# dc_dc.net
KiCad netlist of a schematic drawn in Altium Designer
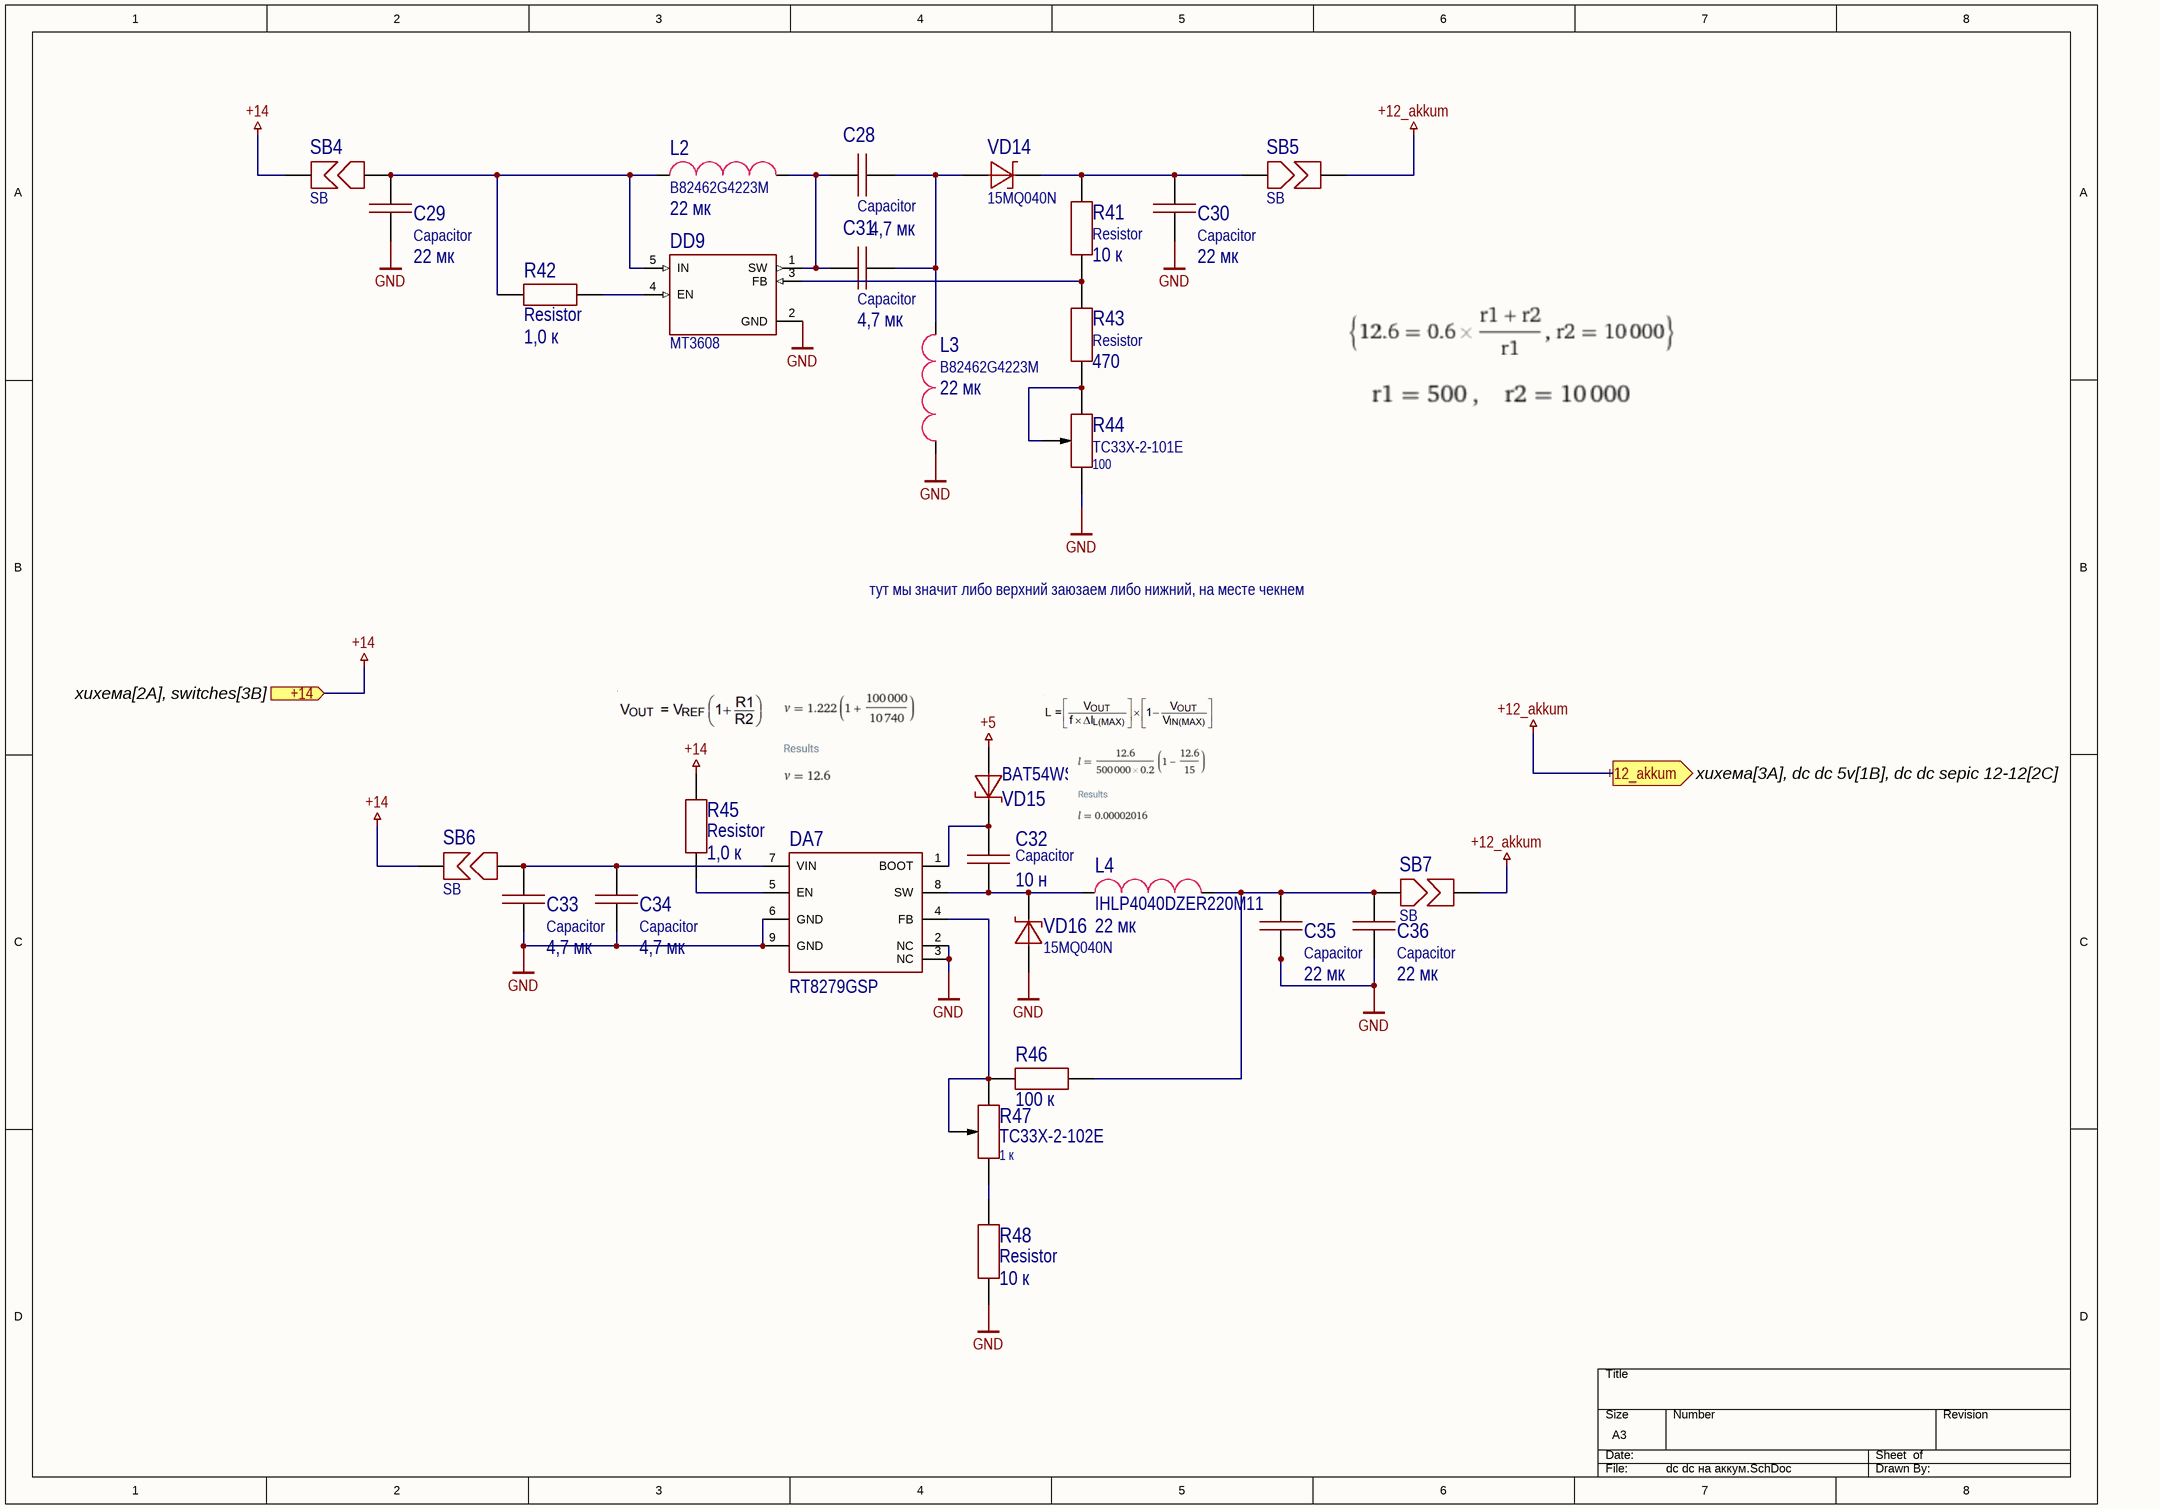
[diagram p0: dc dc на аккум.SchDoc]

(export (version "E")
  (design (tool "Eeschema 10.0.6"))
  (components
    (comp (ref "C28")
      (value "Capacitor")
      (footprint "1206C")
      (description "Конденсатор")
      (fields
        (field (name "ALTIUM_VALUE") "4,7 мк")
        (field (name "PART NUMBER") "Capacitor_4,7u_10_50V_X7R_1206C")
        (field (name "TOLERANCE") "0,1")
      )
      (libsource (lib "Hydrolib") (part "Capacitor"))
    )
    (comp (ref "C29")
      (value "Capacitor")
      (footprint "1210C")
      (description "Конденсатор")
      (fields
        (field (name "ALTIUM_VALUE") "22 мк")
        (field (name "PART NUMBER") "Capacitor_22u_10_25V_X7R_1210C")
        (field (name "TOLERANCE") "0,1")
      )
      (libsource (lib "Hydrolib") (part "Capacitor"))
    )
    (comp (ref "C30")
      (value "Capacitor")
      (footprint "1210C")
      (description "Конденсатор")
      (fields
        (field (name "ALTIUM_VALUE") "22 мк")
        (field (name "PART NUMBER") "Capacitor_22u_10_25V_X7R_1210C")
        (field (name "TOLERANCE") "0,1")
      )
      (libsource (lib "Hydrolib") (part "Capacitor"))
    )
    (comp (ref "C31")
      (value "Capacitor")
      (footprint "1206C")
      (description "Конденсатор")
      (fields
        (field (name "ALTIUM_VALUE") "4,7 мк")
        (field (name "PART NUMBER") "Capacitor_4,7u_10_50V_X7R_1206C")
        (field (name "TOLERANCE") "0,1")
      )
      (libsource (lib "Hydrolib") (part "Capacitor"))
    )
    (comp (ref "C32")
      (value "Capacitor")
      (footprint "0603C")
      (description "Конденсатор")
      (fields
        (field (name "ALTIUM_VALUE") "10 н")
        (field (name "PART NUMBER") "Capacitor_10n_10_50V_X7R_0603C")
        (field (name "TOLERANCE") "0,1")
      )
      (libsource (lib "Hydrolib") (part "Capacitor"))
    )
    (comp (ref "C33")
      (value "Capacitor")
      (footprint "1206C")
      (description "Конденсатор")
      (fields
        (field (name "ALTIUM_VALUE") "4,7 мк")
        (field (name "PART NUMBER") "Capacitor_4,7u_10_50V_X7R_1206C")
        (field (name "TOLERANCE") "0,1")
      )
      (libsource (lib "Hydrolib") (part "Capacitor"))
    )
    (comp (ref "C34")
      (value "Capacitor")
      (footprint "1206C")
      (description "Конденсатор")
      (fields
        (field (name "ALTIUM_VALUE") "4,7 мк")
        (field (name "PART NUMBER") "Capacitor_4,7u_10_50V_X7R_1206C")
        (field (name "TOLERANCE") "0,1")
      )
      (libsource (lib "Hydrolib") (part "Capacitor"))
    )
    (comp (ref "C35")
      (value "Capacitor")
      (footprint "1210C")
      (description "Конденсатор")
      (fields
        (field (name "ALTIUM_VALUE") "22 мк")
        (field (name "PART NUMBER") "Capacitor_22u_10_25V_X7R_1210C")
        (field (name "TOLERANCE") "0,1")
      )
      (libsource (lib "Hydrolib") (part "Capacitor"))
    )
    (comp (ref "C36")
      (value "Capacitor")
      (footprint "1210C")
      (description "Конденсатор")
      (fields
        (field (name "ALTIUM_VALUE") "22 мк")
        (field (name "PART NUMBER") "Capacitor_22u_10_25V_X7R_1210C")
        (field (name "TOLERANCE") "0,1")
      )
      (libsource (lib "Hydrolib") (part "Capacitor"))
    )
    (comp (ref "DA7")
      (value "RT8279GSP")
      (footprint "8SOP(Exposed_Pad)")
      (description "Преобразователь постоянного тока понижающий подстраиваемый выход 5А")
      (libsource (lib "Hydrolib") (part "RT8279GSP"))
    )
    (comp (ref "DD9")
      (value "MT3608")
      (footprint "SOT23-6")
      (description "Повышающий/SEPIC DC-DC преобразователь 2А 1.2МГц")
      (libsource (lib "Hydrolib") (part "MT3608"))
    )
    (comp (ref "L2")
      (value "B82462G4223M")
      (footprint "B82462G4")
      (description "ЧИП-индуктивность 22мкГн, 1.05A, ±20% катушка")
      (fields (field (name "ALTIUM_VALUE") "22 мк"))
      (libsource (lib "Hydrolib") (part "Inductance"))
    )
    (comp (ref "L3")
      (value "B82462G4223M")
      (footprint "B82462G4")
      (description "ЧИП-индуктивность 22мкГн, 1.05A, ±20% катушка")
      (fields (field (name "ALTIUM_VALUE") "22 мк"))
      (libsource (lib "Hydrolib") (part "Inductance"))
    )
    (comp (ref "L4")
      (value "IHLP4040DZER220M11")
      (footprint "IHLP-4040")
      (description "ЧИП-индуктивность экранированная 22мкГн ±20% 5A 66мОм 4040 лента на катушке")
      (fields (field (name "ALTIUM_VALUE") "22 мк"))
      (libsource (lib "Hydrolib") (part "Inductance"))
    )
    (comp (ref "R41")
      (value "Resistor")
      (footprint "0603R")
      (description "Резистор номиналом 10 кОм и точностью 1%")
      (fields
        (field (name "ALTIUM_VALUE") "10 к")
        (field (name "PART NUMBER") "Resistor_10k_1_0603")
        (field (name "TOLERANCE") "1%")
      )
      (libsource (lib "") (part "Resistor_1"))
    )
    (comp (ref "R42")
      (value "Resistor")
      (footprint "0603R")
      (description "Резистор номиналом 1,0 кОм и точностью 1%")
      (fields
        (field (name "ALTIUM_VALUE") "1,0 к")
        (field (name "PART NUMBER") "Resistor_1.0k_1_0603")
        (field (name "TOLERANCE") "1%")
      )
      (libsource (lib "Hydrolib") (part "Resistor"))
    )
    (comp (ref "R43")
      (value "Resistor")
      (footprint "0603R")
      (description "Резистор номиналом 470 Ом и точностью 1%")
      (fields
        (field (name "ALTIUM_VALUE") "470")
        (field (name "PART NUMBER") "Resistor_470_1_0603")
        (field (name "TOLERANCE") "1%")
      )
      (libsource (lib "") (part "Resistor_1"))
    )
    (comp (ref "R44")
      (value "TC33X-2-101E")
      (footprint "3mm_trim")
      (description "Потенциометр керметный 100 Ом 0.1Вт для поверхностного монтажа")
      (fields (field (name "ALTIUM_VALUE") "100") (field (name "TOLERANCE") "50%"))
      (libsource (lib "Hydrolib") (part "trim_res"))
    )
    (comp (ref "R45")
      (value "Resistor")
      (footprint "0603R")
      (description "Резистор номиналом 1,0 кОм и точностью 1%")
      (fields
        (field (name "ALTIUM_VALUE") "1,0 к")
        (field (name "PART NUMBER") "Resistor_1.0k_1_0603")
        (field (name "TOLERANCE") "1%")
      )
      (libsource (lib "") (part "Resistor_1"))
    )
    (comp (ref "R46")
      (value "100 к")
      (footprint "0603R")
      (description "Резистор номиналом 100 кОм и точностью 1%")
      (fields (field (name "PART NUMBER") "Resistor_100k_1_0603") (field (name "TOLERANCE") "1%"))
      (libsource (lib "") (part "Resistor_2"))
    )
    (comp (ref "R47")
      (value "TC33X-2-102E")
      (footprint "3mm_trim")
      (description "Потенциометр керметный 1кОм 0.1Вт для поверхностного монтажа")
      (fields (field (name "ALTIUM_VALUE") "1 к") (field (name "TOLERANCE") "50%"))
      (libsource (lib "Hydrolib") (part "trim_res"))
    )
    (comp (ref "R48")
      (value "Resistor")
      (footprint "0603R")
      (description "Резистор номиналом 10 кОм и точностью 1%")
      (fields
        (field (name "ALTIUM_VALUE") "10 к")
        (field (name "PART NUMBER") "Resistor_10k_1_0603")
        (field (name "TOLERANCE") "1%")
      )
      (libsource (lib "") (part "Resistor_1"))
    )
    (comp (ref "SB4")
      (value "SB")
      (footprint "1206SB")
      (description "Solder bridge, мост припоя, запаиваемая перемычка, net tie, jumper")
      (libsource (lib "Hydrolib") (part "SB"))
    )
    (comp (ref "SB5")
      (value "SB")
      (footprint "1206SB")
      (description "Solder bridge, мост припоя, запаиваемая перемычка, net tie, jumper")
      (libsource (lib "Hydrolib") (part "SB"))
    )
    (comp (ref "SB6")
      (value "SB")
      (footprint "1206SB")
      (description "Solder bridge, мост припоя, запаиваемая перемычка, net tie, jumper")
      (libsource (lib "Hydrolib") (part "SB"))
    )
    (comp (ref "SB7")
      (value "SB")
      (footprint "1206SB")
      (description "Solder bridge, мост припоя, запаиваемая перемычка, net tie, jumper")
      (libsource (lib "Hydrolib") (part "SB"))
    )
    (comp (ref "VD14")
      (value "15MQ040N")
      (footprint "SMA")
      (description "Диод шоттки на 40 В, ном. ток 2.1 А")
      (libsource (lib "Hydrolib") (part "Schottky_diode"))
    )
    (comp (ref "VD15")
      (value "BAT54WS")
      (footprint "SOD-323")
      (description "Диод шоттки на 30 В, ном. ток 0.2 А")
      (libsource (lib "Hydrolib") (part "Schottky_diode"))
    )
    (comp (ref "VD16")
      (value "15MQ040N")
      (footprint "SMA")
      (description "Диод шоттки на 40 В, ном. ток 2.1 А")
      (libsource (lib "Hydrolib") (part "Schottky_diode"))
    )
  )
  (nets
    (net (code "1") (name "+5") (class "Default")
      (node (ref "VD15") (pin "1") (pinfunction "1_1") (pintype "passive"))
    )
    (net (code "2") (name "+12_akkum") (class "Default")
      (node (ref "SB5") (pin "1") (pinfunction "1_1") (pintype "passive"))
      (node (ref "SB7") (pin "1") (pinfunction "1_1") (pintype "passive"))
    )
    (net (code "3") (name "+14") (class "Default")
      (node (ref "R45") (pin "2") (pinfunction "2_2") (pintype "passive"))
      (node (ref "SB4") (pin "1") (pinfunction "1_1") (pintype "passive"))
      (node (ref "SB6") (pin "1") (pinfunction "1_1") (pintype "passive"))
    )
    (net (code "4") (name "GND") (class "Default")
      (node (ref "C29") (pin "1") (pinfunction "1_1") (pintype "passive"))
      (node (ref "C30") (pin "1") (pinfunction "1_1") (pintype "passive"))
      (node (ref "C33") (pin "1") (pinfunction "1_1") (pintype "passive"))
      (node (ref "C34") (pin "1") (pinfunction "1_1") (pintype "passive"))
      (node (ref "C35") (pin "1") (pinfunction "1_1") (pintype "passive"))
      (node (ref "C36") (pin "1") (pinfunction "1_1") (pintype "passive"))
      (node (ref "DA7") (pin "2") (pinfunction "NC_2") (pintype "passive"))
      (node (ref "DA7") (pin "3") (pinfunction "NC_3") (pintype "passive"))
      (node (ref "DA7") (pin "6") (pinfunction "GND_6") (pintype "passive"))
      (node (ref "DA7") (pin "9") (pinfunction "GND_9") (pintype "passive"))
      (node (ref "DD9") (pin "2") (pinfunction "GND_2") (pintype "power_in"))
      (node (ref "L3") (pin "1") (pinfunction "1_1") (pintype "passive"))
      (node (ref "R44") (pin "1") (pinfunction "1_1") (pintype "passive"))
      (node (ref "R48") (pin "1") (pinfunction "1_1") (pintype "passive"))
      (node (ref "VD16") (pin "1") (pinfunction "1_1") (pintype "passive"))
    )
    (net (code "5") (name "Net-(C28-Pad2)") (class "Default")
      (node (ref "C28") (pin "2") (pinfunction "2_2") (pintype "passive"))
      (node (ref "C31") (pin "2") (pinfunction "2_2") (pintype "passive"))
      (node (ref "L3") (pin "2") (pinfunction "2_2") (pintype "passive"))
      (node (ref "VD14") (pin "1") (pinfunction "1_1") (pintype "passive"))
    )
    (net (code "6") (name "Net-(C30-Pad2)") (class "Default")
      (node (ref "C30") (pin "2") (pinfunction "2_2") (pintype "passive"))
      (node (ref "R41") (pin "2") (pinfunction "2_2") (pintype "passive"))
      (node (ref "SB5") (pin "2") (pinfunction "2_2") (pintype "passive"))
      (node (ref "VD14") (pin "2") (pinfunction "2_2") (pintype "passive"))
    )
    (net (code "7") (name "Net-(C35-Pad2)") (class "Default")
      (node (ref "C35") (pin "2") (pinfunction "2_2") (pintype "passive"))
      (node (ref "C36") (pin "2") (pinfunction "2_2") (pintype "passive"))
      (node (ref "L4") (pin "2") (pinfunction "2_2") (pintype "passive"))
      (node (ref "R46") (pin "2") (pinfunction "2_2") (pintype "passive"))
      (node (ref "SB7") (pin "2") (pinfunction "2_2") (pintype "passive"))
    )
    (net (code "8") (name "Net-(DA7-BOOT)") (class "Default")
      (node (ref "C32") (pin "2") (pinfunction "2_2") (pintype "passive"))
      (node (ref "DA7") (pin "1") (pinfunction "BOOT_1") (pintype "passive"))
      (node (ref "VD15") (pin "2") (pinfunction "2_2") (pintype "passive"))
    )
    (net (code "9") (name "Net-(DA7-EN)") (class "Default")
      (node (ref "DA7") (pin "5") (pinfunction "EN_5") (pintype "passive"))
      (node (ref "R45") (pin "1") (pinfunction "1_1") (pintype "passive"))
    )
    (net (code "10") (name "Net-(DA7-FB)") (class "Default")
      (node (ref "DA7") (pin "4") (pinfunction "FB_4") (pintype "passive"))
      (node (ref "R46") (pin "1") (pinfunction "1_1") (pintype "passive"))
      (node (ref "R47") (pin "2") (pinfunction "2_2") (pintype "passive"))
      (node (ref "R47") (pin "3") (pinfunction "3_3") (pintype "passive"))
    )
    (net (code "11") (name "Net-(DA7-SW)") (class "Default")
      (node (ref "C32") (pin "1") (pinfunction "1_1") (pintype "passive"))
      (node (ref "DA7") (pin "8") (pinfunction "SW_8") (pintype "passive"))
      (node (ref "L4") (pin "1") (pinfunction "1_1") (pintype "passive"))
      (node (ref "VD16") (pin "2") (pinfunction "2_2") (pintype "passive"))
    )
    (net (code "12") (name "Net-(DA7-VIN)") (class "Default")
      (node (ref "C33") (pin "2") (pinfunction "2_2") (pintype "passive"))
      (node (ref "C34") (pin "2") (pinfunction "2_2") (pintype "passive"))
      (node (ref "DA7") (pin "7") (pinfunction "VIN_7") (pintype "passive"))
      (node (ref "SB6") (pin "2") (pinfunction "2_2") (pintype "passive"))
    )
    (net (code "13") (name "Net-(DD9-EN)") (class "Default")
      (node (ref "DD9") (pin "4") (pinfunction "EN_4") (pintype "input"))
      (node (ref "R42") (pin "1") (pinfunction "1_1") (pintype "passive"))
    )
    (net (code "14") (name "Net-(DD9-FB)") (class "Default")
      (node (ref "DD9") (pin "3") (pinfunction "FB_3") (pintype "input"))
      (node (ref "R41") (pin "1") (pinfunction "1_1") (pintype "passive"))
      (node (ref "R43") (pin "2") (pinfunction "2_2") (pintype "passive"))
    )
    (net (code "15") (name "Net-(DD9-IN)") (class "Default")
      (node (ref "C29") (pin "2") (pinfunction "2_2") (pintype "passive"))
      (node (ref "DD9") (pin "5") (pinfunction "IN_5") (pintype "input"))
      (node (ref "L2") (pin "1") (pinfunction "1_1") (pintype "passive"))
      (node (ref "R42") (pin "2") (pinfunction "2_2") (pintype "passive"))
      (node (ref "SB4") (pin "2") (pinfunction "2_2") (pintype "passive"))
    )
    (net (code "16") (name "Net-(DD9-SW)") (class "Default")
      (node (ref "C28") (pin "1") (pinfunction "1_1") (pintype "passive"))
      (node (ref "C31") (pin "1") (pinfunction "1_1") (pintype "passive"))
      (node (ref "DD9") (pin "1") (pinfunction "SW_1") (pintype "output"))
      (node (ref "L2") (pin "2") (pinfunction "2_2") (pintype "passive"))
    )
    (net (code "17") (name "Net-(R43-Pad1)") (class "Default")
      (node (ref "R43") (pin "1") (pinfunction "1_1") (pintype "passive"))
      (node (ref "R44") (pin "2") (pinfunction "2_2") (pintype "passive"))
      (node (ref "R44") (pin "3") (pinfunction "3_3") (pintype "passive"))
    )
    (net (code "18") (name "Net-(R47-Pad1)") (class "Default")
      (node (ref "R47") (pin "1") (pinfunction "1_1") (pintype "passive"))
      (node (ref "R48") (pin "2") (pinfunction "2_2") (pintype "passive"))
    )
  )
)
